# Driver_Esq.net
KiCad netlist of a schematic drawn in Altium Designer
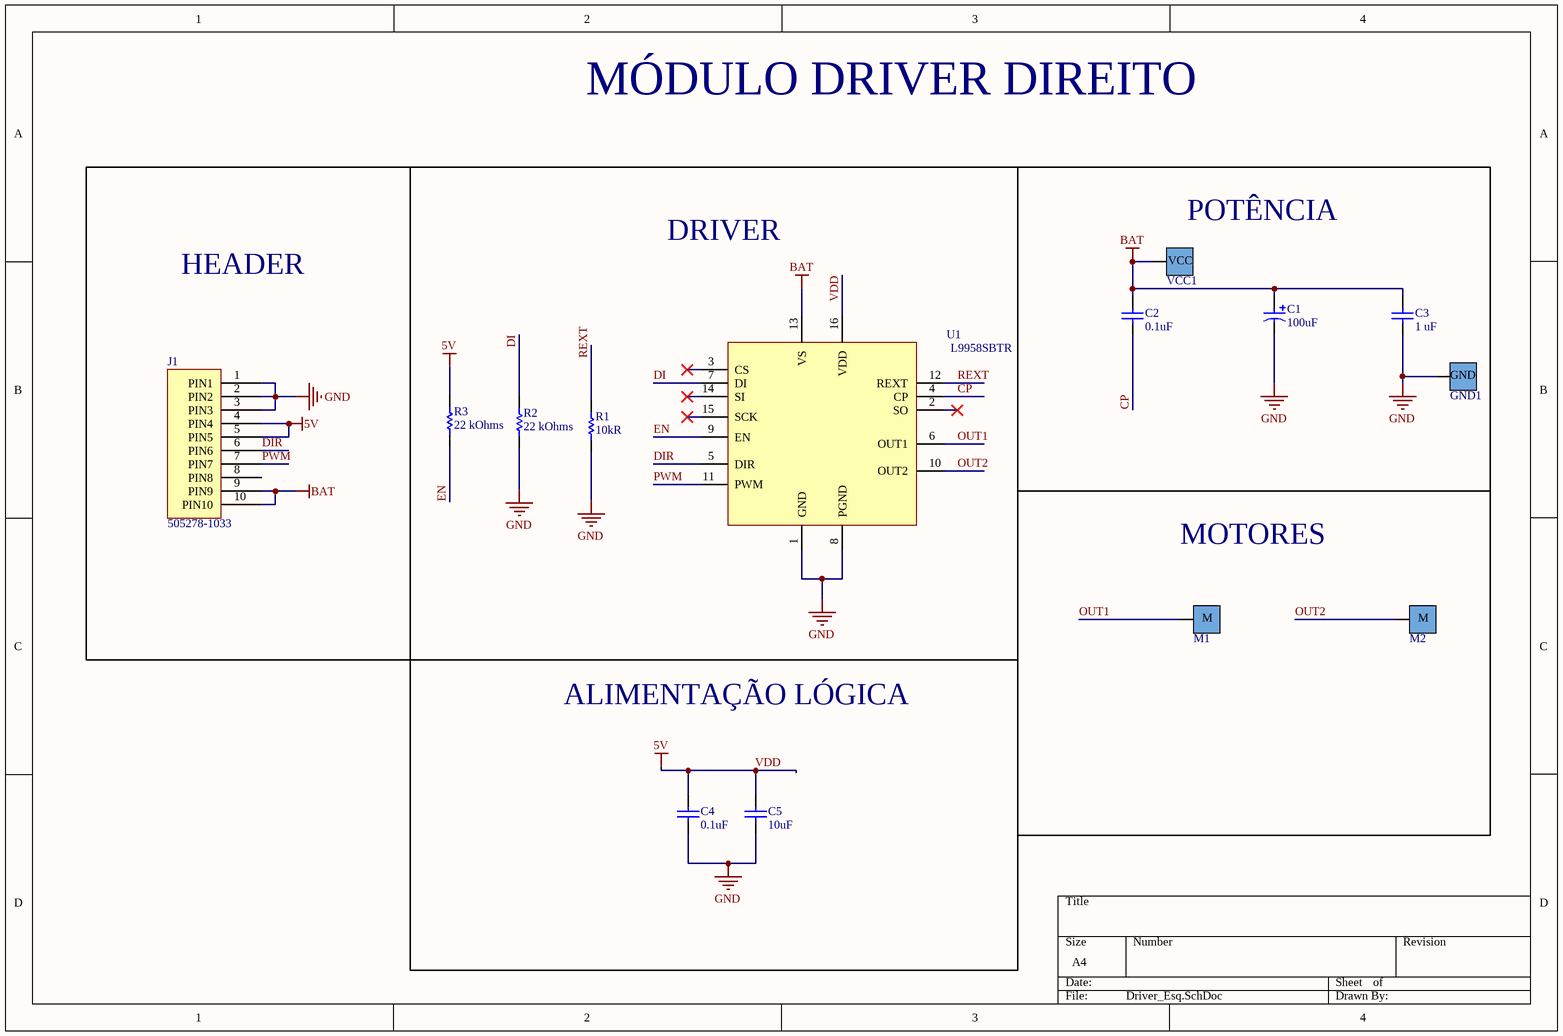
[diagram p0: Driver_Esq.SchDoc]

(export (version "E")
  (design (tool "Eeschema 10.0.6"))
  (components
    (comp (ref "C1")
      (value "100uF")
      (footprint "TANTALUM C0805")
      (description "CAP TAN 100uF 6.3V 0805")
      (fields
        (field (name "MANUFACTURER") "AVX")
        (field (name "PART NUMBER") "F980J107MSA")
        (field (name "LIBRARY CONTROL - PERSON THAT CHECKED FOOTPRINT") "Nikaum")
        (field (name "LIBRARY CONTROL - PERSON THAT CHECKED SCHEMATIC") "Nikaum")
        (field (name "LIBRARY CONTROL - PERSON THAT DID THE LAST UPDATE FOOTPRINT") "Nikaum")
        (field (name "LIBRARY CONTROL - PERSON THAT DID THE LAST UPDATE SCHEMATIC") "Nikaum")
      )
      (libsource (lib "Uai!Tecas") (part "F980J107MSA"))
    )
    (comp (ref "C2")
      (value "0.1uF")
      (footprint "C0805")
      (description "CAP CER 100nF 25V X7R 0805")
      (fields
        (field (name "MANUFACTURER") "Kemet")
        (field (name "PART NUMBER") "C0805C104M3RACTU")
        (field (name "LIBRARY CONTROL - PERSON THAT CHECKED FOOTPRINT") "Cage")
        (field (name "LIBRARY CONTROL - PERSON THAT CHECKED SCHEMATIC") "Cage")
        (field (name "LIBRARY CONTROL - PERSON THAT DID THE LAST UPDATE FOOTPRINT") "Cage")
        (field (name "LIBRARY CONTROL - PERSON THAT DID THE LAST UPDATE SCHEMATIC") "Cage")
      )
      (libsource (lib "Uai!Tecas") (part "C0805C104M3RACTU"))
    )
    (comp (ref "C3")
      (value "1 uF")
      (footprint "C0805")
      (description "CAP CER 1uF 100V X7R 0805")
      (fields (field (name "MANUFACTURER") "KYOCERA AVX") (field (name "PART NUMBER") "08051C105K4T2A"))
      (libsource (lib "Uai!Tecas") (part "08051C105K4T2A"))
    )
    (comp (ref "C4")
      (value "0.1uF")
      (footprint "C0805")
      (description "CAP CER 100nF 25V X7R 0805")
      (fields
        (field (name "MANUFACTURER") "Kemet")
        (field (name "PART NUMBER") "C0805C104M3RACTU")
        (field (name "LIBRARY CONTROL - PERSON THAT CHECKED FOOTPRINT") "Cage")
        (field (name "LIBRARY CONTROL - PERSON THAT CHECKED SCHEMATIC") "Cage")
        (field (name "LIBRARY CONTROL - PERSON THAT DID THE LAST UPDATE FOOTPRINT") "Cage")
        (field (name "LIBRARY CONTROL - PERSON THAT DID THE LAST UPDATE SCHEMATIC") "Cage")
      )
      (libsource (lib "Uai!Tecas") (part "C0805C104M3RACTU"))
    )
    (comp (ref "C5")
      (value "10uF")
      (footprint "C0805")
      (description "CAP CER 10uF 16V X7R 0805")
      (fields
        (field (name "MANUFACTURER") "Taiyo Yuden")
        (field (name "PART NUMBER") "EMK212BB7106MG-T")
        (field (name "LIBRARY CONTROL - PERSON THAT CHECKED FOOTPRINT") "Cage")
        (field (name "LIBRARY CONTROL - PERSON THAT CHECKED SCHEMATIC") "Cage")
        (field (name "LIBRARY CONTROL - PERSON THAT DID THE LAST UPDATE FOOTPRINT") "Chico")
        (field (name "LIBRARY CONTROL - PERSON THAT DID THE LAST UPDATE SCHEMATIC") "Cage")
      )
      (libsource (lib "Uai!Tecas") (part "EMK212BB7106MG-T"))
    )
    (comp (ref "GND1")
      (value "Ground Pad")
      (footprint "PAD_ALIMENTAÇÃO_MINI")
      (description "GND PAD MINI SUMÔ")
      (libsource (lib "Uai!Tecas") (part "Ground Pad Mini Sumô"))
    )
    (comp (ref "J1")
      (value "505278-1033")
      (footprint "FPC_CON")
      (description "CONN FFC/FPC HORZ 10POS 0.50MM")
      (fields
        (field (name "MANUFACTURER") "Molex")
        (field (name "LIBRARY CONTROL - PERSON THAT CHECKED FOOTPRINT") "Lucas")
        (field (name "LIBRARY CONTROL - PERSON THAT CHECKED SCHEMATIC") "Lucas")
        (field (name "LIBRARY CONTROL - PERSON THAT DID THE LAST UPDATE FOOTPRINT") "Mateus(Dimas)")
        (field (name "LIBRARY CONTROL - PERSON THAT DID THE LAST UPDATE SCHEMATIC") "Mateus(Dimas)")
      )
      (libsource (lib "Uai!Tecas") (part "505278-1033_BODY"))
    )
    (comp (ref "M1")
      (value "Motor Pad")
      (footprint "PAD_MOTOR_MINI")
      (description "MOTOR PAD MINI SUMÔ")
      (libsource (lib "Uai!Tecas") (part "Motor Pad Mini Sumô"))
    )
    (comp (ref "M2")
      (value "Motor Pad")
      (footprint "PAD_MOTOR_MINI")
      (description "MOTOR PAD MINI SUMÔ")
      (libsource (lib "Uai!Tecas") (part "Motor Pad Mini Sumô"))
    )
    (comp (ref "R1")
      (value "10kR")
      (footprint "RESISTOR_0603")
      (description "RES SMD 10K OHM 5% 1/10W 0603")
      (fields
        (field (name "MANUFACTURER") "Yageo")
        (field (name "PART NUMBER") "RC0603JR-0710KL")
        (field (name "LIBRARY CONTROL - PERSON THAT CHECKED SCHEMATIC") "Marcos")
        (field (name "LIBRARY CONTROL - PERSON THAT DID THE LAST UPDATE FOOTPRINT") "Dalarme")
        (field (name "LIBRARY CONTROL - PERSON THAT DID THE LAST UPDATE SCHEMATIC") "Marcos")
      )
      (libsource (lib "Uai!Tecas") (part "RC0603JR-0710KL"))
    )
    (comp (ref "R2")
      (value "22 kOhms")
      (footprint "RESISTOR_0603")
      (description "RES SMD 22K OHM 1% 1/5W 0603")
      (fields
        (field (name "MANUFACTURER") "TE Connectivity / Holsworthy")
        (field (name "PART NUMBER") "CRGH0603F22K")
      )
      (libsource (lib "Uai!Tecas") (part "CRGH0603F22K"))
    )
    (comp (ref "R3")
      (value "22 kOhms")
      (footprint "RESISTOR_0603")
      (description "RES SMD 22K OHM 1% 1/5W 0603")
      (fields
        (field (name "MANUFACTURER") "TE Connectivity / Holsworthy")
        (field (name "PART NUMBER") "CRGH0603F22K")
      )
      (libsource (lib "Uai!Tecas") (part "CRGH0603F22K"))
    )
    (comp (ref "U1")
      (value "L9958SBTR")
      (footprint "POWERSO16 (16_PINS)")
      (description "IC MTR DRV (4V ~ 28V) (100 uA) POWERSO 16")
      (fields
        (field (name "MANUFACTURER") "ST")
        (field (name "LIBRARY CONTROL - PERSON THAT CHECKED SCHEMATIC") "Pierre")
        (field (name "LIBRARY CONTROL - PERSON THAT CHECKED FOOTPRINT") "Pierre")
        (field (name "LIBRARY CONTROL - PERSON THAT DID THE LAST UPDATE SCHEMATIC") "Pierre")
        (field (name "LIBRARY CONTROL - PERSON THAT DID THE LAST UPDATE FOOTPRINT") "Stéfany(Ster)")
      )
      (libsource (lib "Driver") (part "L9958SBTR"))
    )
    (comp (ref "VCC1")
      (value "Source Pad")
      (footprint "PAD_ALIMENTAÇÃO_MINI")
      (description "VCC PAD MINI SUMÔ")
      (libsource (lib "Uai!Tecas") (part "Source Pad Mini Sumô"))
    )
  )
  (nets
    (net (code "1") (name "/CP") (class "Default")
      (node (ref "C2") (pin "2") (pinfunction "2_2") (pintype "passive"))
      (node (ref "U1") (pin "4") (pinfunction "CP_4") (pintype "passive"))
    )
    (net (code "2") (name "/DI") (class "Default")
      (node (ref "R2") (pin "2") (pinfunction "2_2") (pintype "passive"))
      (node (ref "U1") (pin "7") (pinfunction "DI_7") (pintype "passive"))
    )
    (net (code "3") (name "/DIR") (class "Default")
      (node (ref "J1") (pin "6") (pinfunction "PIN6_6") (pintype "passive"))
      (node (ref "U1") (pin "5") (pinfunction "DIR_5") (pintype "passive"))
    )
    (net (code "4") (name "/EN") (class "Default")
      (node (ref "R3") (pin "2") (pinfunction "2_2") (pintype "passive"))
      (node (ref "U1") (pin "9") (pinfunction "EN_9") (pintype "passive"))
    )
    (net (code "5") (name "/OUT1") (class "Default")
      (node (ref "M1") (pin "M") (pinfunction "M_M") (pintype "passive"))
      (node (ref "U1") (pin "6") (pinfunction "OUT1_6") (pintype "passive"))
    )
    (net (code "6") (name "/OUT2") (class "Default")
      (node (ref "M2") (pin "M") (pinfunction "M_M") (pintype "passive"))
      (node (ref "U1") (pin "10") (pinfunction "OUT2_10") (pintype "passive"))
    )
    (net (code "7") (name "/PWM") (class "Default")
      (node (ref "J1") (pin "7") (pinfunction "PIN7_7") (pintype "passive"))
      (node (ref "U1") (pin "11") (pinfunction "PWM_11") (pintype "passive"))
    )
    (net (code "8") (name "/REXT") (class "Default")
      (node (ref "R1") (pin "2") (pinfunction "2_2") (pintype "passive"))
      (node (ref "U1") (pin "12") (pinfunction "REXT_12") (pintype "passive"))
    )
    (net (code "9") (name "5V") (class "Default")
      (node (ref "C4") (pin "1") (pinfunction "1_1") (pintype "passive"))
      (node (ref "C5") (pin "2") (pinfunction "2_2") (pintype "passive"))
      (node (ref "J1") (pin "4") (pinfunction "PIN4_4") (pintype "passive"))
      (node (ref "J1") (pin "5") (pinfunction "PIN5_5") (pintype "passive"))
      (node (ref "R3") (pin "1") (pinfunction "1_1") (pintype "passive"))
      (node (ref "U1") (pin "16") (pinfunction "VDD_16") (pintype "passive"))
    )
    (net (code "10") (name "BAT") (class "Default")
      (node (ref "C1") (pin "1") (pinfunction "1_1") (pintype "passive"))
      (node (ref "C2") (pin "1") (pinfunction "1_1") (pintype "passive"))
      (node (ref "C3") (pin "2") (pinfunction "2_2") (pintype "passive"))
      (node (ref "J1") (pin "10") (pinfunction "PIN10_10") (pintype "passive"))
      (node (ref "J1") (pin "9") (pinfunction "PIN9_9") (pintype "passive"))
      (node (ref "U1") (pin "13") (pinfunction "VS_13") (pintype "passive"))
      (node (ref "VCC1") (pin "A") (pinfunction "VCC_A") (pintype "passive"))
    )
    (net (code "11") (name "GND") (class "Default")
      (node (ref "C1") (pin "2") (pinfunction "2_2") (pintype "passive"))
      (node (ref "C3") (pin "1") (pinfunction "1_1") (pintype "passive"))
      (node (ref "C4") (pin "2") (pinfunction "2_2") (pintype "passive"))
      (node (ref "C5") (pin "1") (pinfunction "1_1") (pintype "passive"))
      (node (ref "GND1") (pin "A") (pinfunction "GND_A") (pintype "passive"))
      (node (ref "J1") (pin "1") (pinfunction "PIN1_1") (pintype "passive"))
      (node (ref "J1") (pin "2") (pinfunction "PIN2_2") (pintype "passive"))
      (node (ref "J1") (pin "3") (pinfunction "PIN3_3") (pintype "passive"))
      (node (ref "R1") (pin "1") (pinfunction "1_1") (pintype "passive"))
      (node (ref "R2") (pin "1") (pinfunction "1_1") (pintype "passive"))
      (node (ref "U1") (pin "1") (pinfunction "GND_1") (pintype "passive"))
      (node (ref "U1") (pin "8") (pinfunction "PGND_8") (pintype "passive"))
    )
    (net (code "12") (name "unconnected-(J1-PIN8-Pad8)") (class "Default")
      (node (ref "J1") (pin "8") (pinfunction "PIN8_8") (pintype "passive"))
    )
    (net (code "13") (name "unconnected-(U1-CS-Pad3)") (class "Default")
      (node (ref "U1") (pin "3") (pinfunction "CS_3") (pintype "passive+no_connect"))
    )
    (net (code "14") (name "unconnected-(U1-SCK-Pad15)") (class "Default")
      (node (ref "U1") (pin "15") (pinfunction "SCK_15") (pintype "passive+no_connect"))
    )
    (net (code "15") (name "unconnected-(U1-SI-Pad14)") (class "Default")
      (node (ref "U1") (pin "14") (pinfunction "SI_14") (pintype "passive+no_connect"))
    )
    (net (code "16") (name "unconnected-(U1-SO-Pad2)") (class "Default")
      (node (ref "U1") (pin "2") (pinfunction "SO_2") (pintype "passive+no_connect"))
    )
  )
)
